# PCB-BI8-1x12SC3.net
KiCad netlist of a schematic drawn in EAGLE
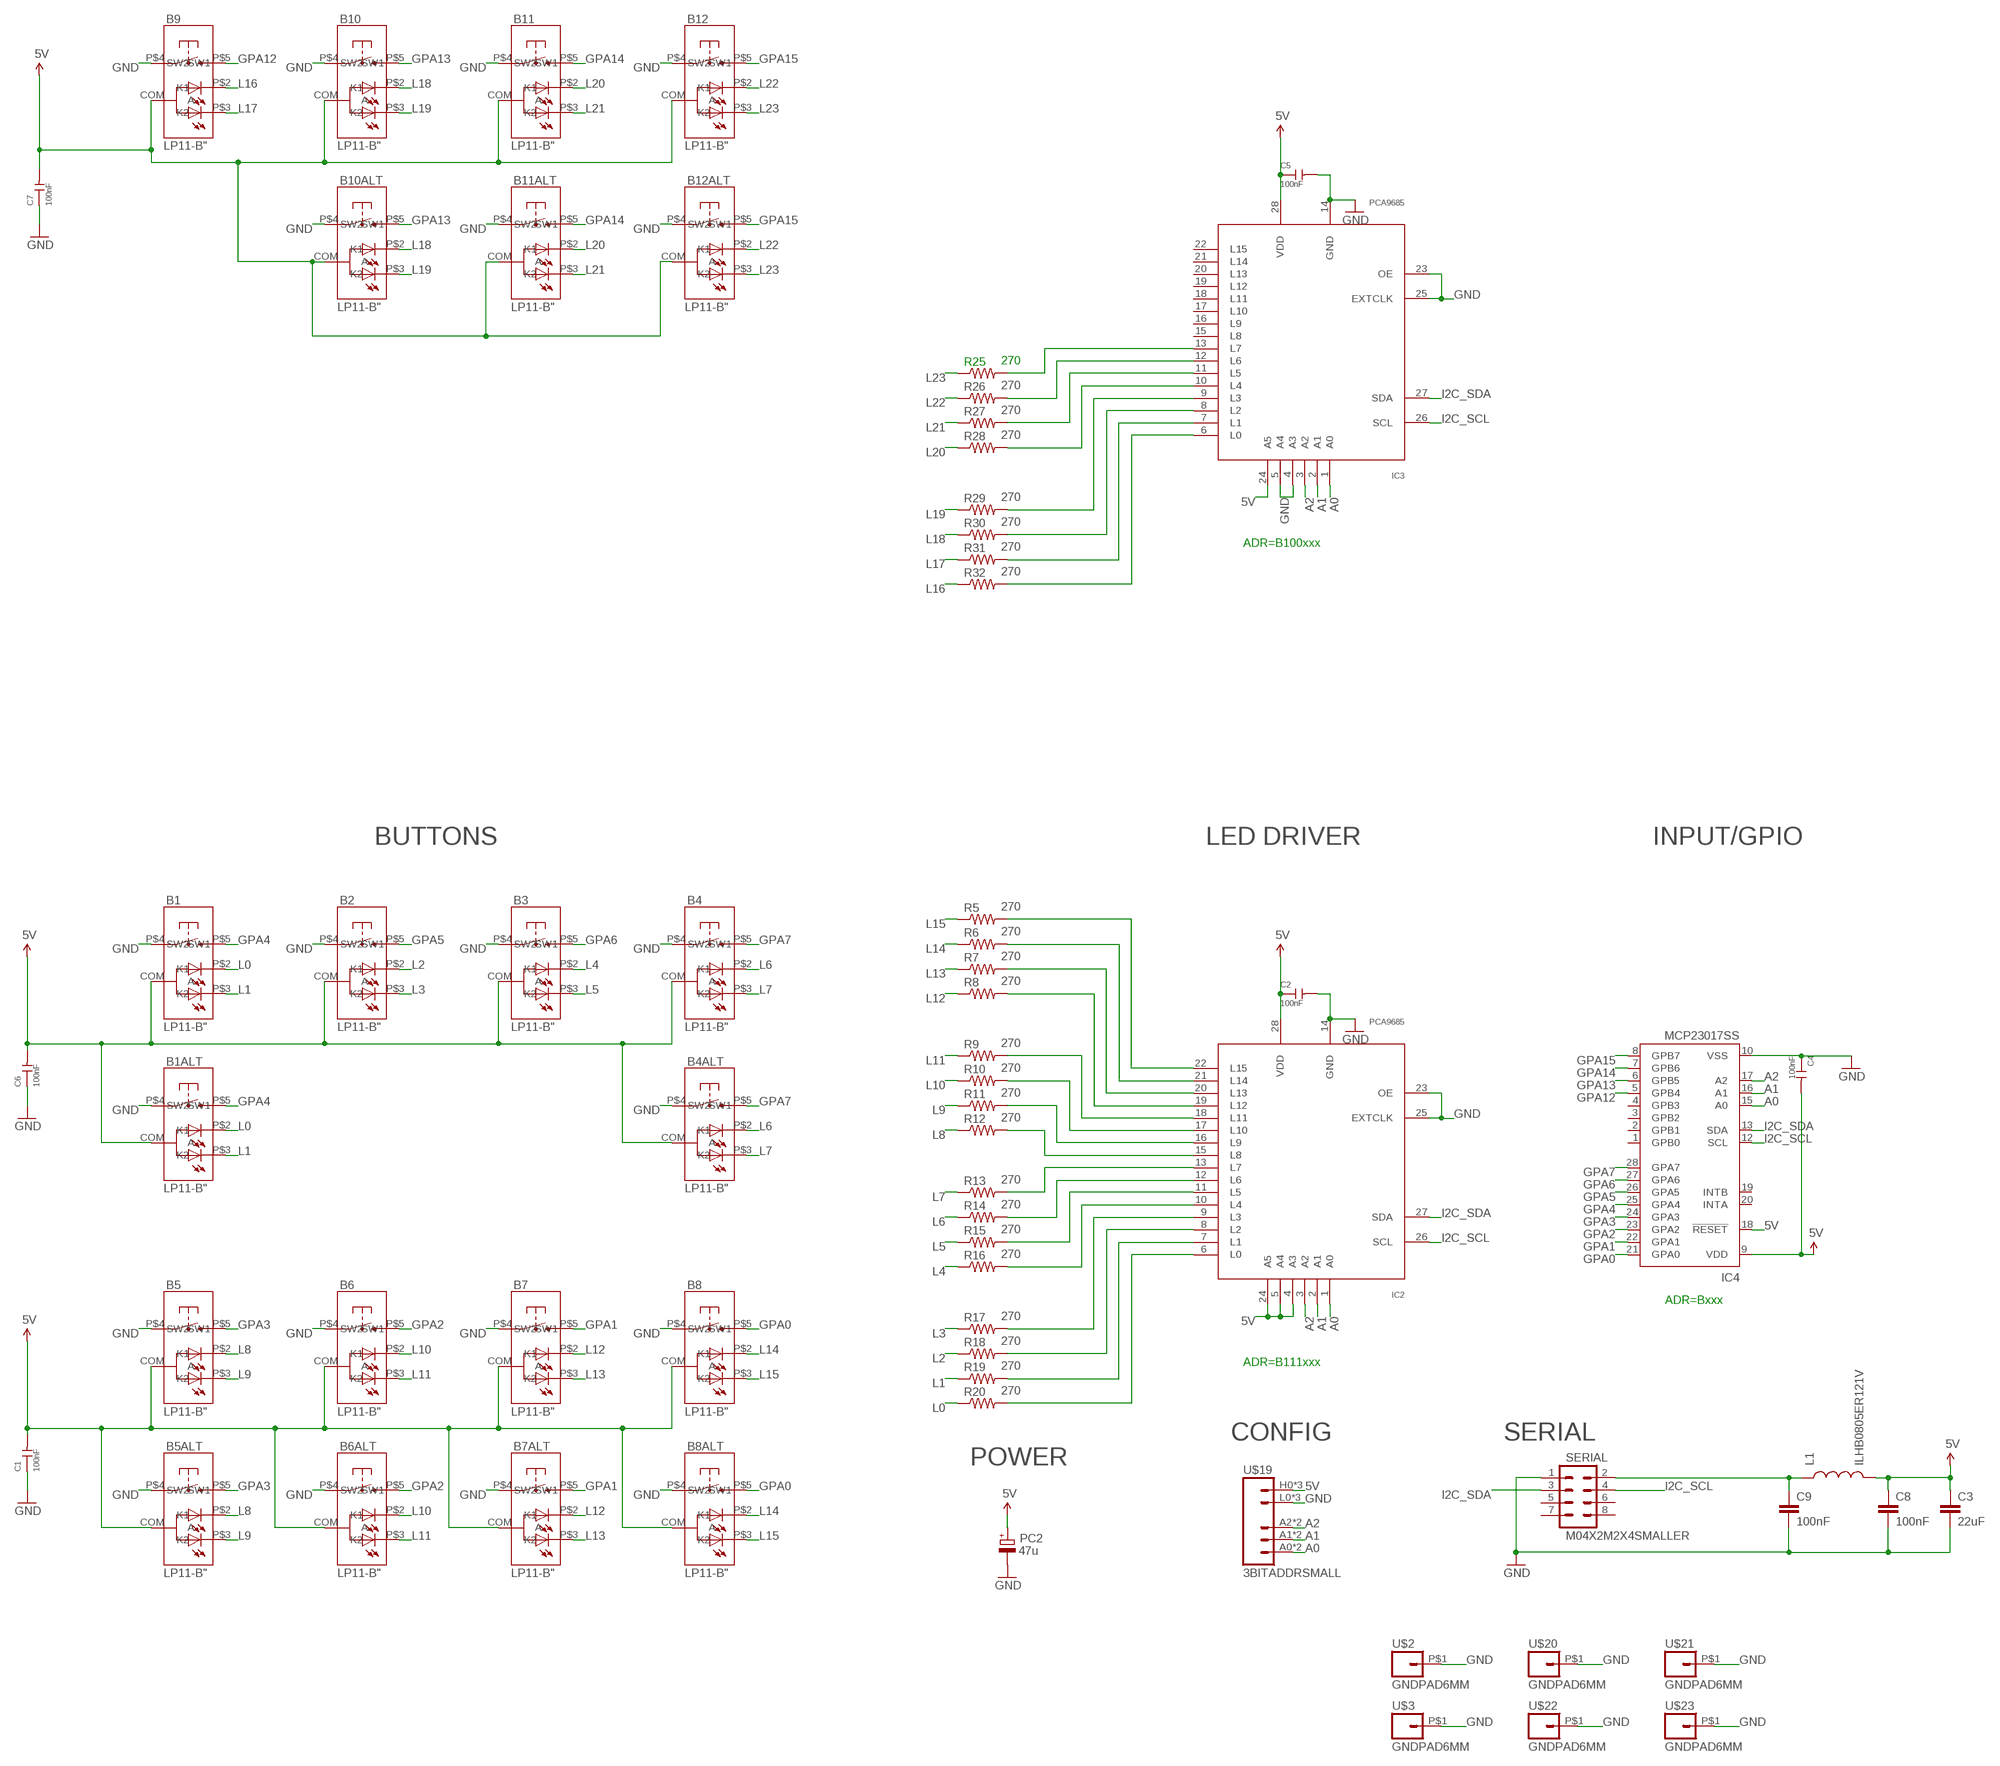
[diagram p0: schematic, sheet 1]

(export (version "E")
  (design (tool "Eeschema 10.0.6"))
  (components
    (comp (ref "B1")
      (value "LP11-B\"")
      (footprint "eagle-import:LP11")
      (libsource (lib "eagle-import") (part "LP11-B{dblquote}"))
    )
    (comp (ref "B1ALT")
      (value "LP11-B\"")
      (footprint "eagle-import:LP11")
      (libsource (lib "eagle-import") (part "LP11-B{dblquote}"))
    )
    (comp (ref "B2")
      (value "LP11-B\"")
      (footprint "eagle-import:LP11")
      (libsource (lib "eagle-import") (part "LP11-B{dblquote}"))
    )
    (comp (ref "B3")
      (value "LP11-B\"")
      (footprint "eagle-import:LP11")
      (libsource (lib "eagle-import") (part "LP11-B{dblquote}"))
    )
    (comp (ref "B4")
      (value "LP11-B\"")
      (footprint "eagle-import:LP11")
      (libsource (lib "eagle-import") (part "LP11-B{dblquote}"))
    )
    (comp (ref "B4ALT")
      (value "LP11-B\"")
      (footprint "eagle-import:LP11")
      (libsource (lib "eagle-import") (part "LP11-B{dblquote}"))
    )
    (comp (ref "B5")
      (value "LP11-B\"")
      (footprint "eagle-import:LP11")
      (libsource (lib "eagle-import") (part "LP11-B{dblquote}"))
    )
    (comp (ref "B5ALT")
      (value "LP11-B\"")
      (footprint "eagle-import:LP11")
      (libsource (lib "eagle-import") (part "LP11-B{dblquote}"))
    )
    (comp (ref "B6")
      (value "LP11-B\"")
      (footprint "eagle-import:LP11")
      (libsource (lib "eagle-import") (part "LP11-B{dblquote}"))
    )
    (comp (ref "B6ALT")
      (value "LP11-B\"")
      (footprint "eagle-import:LP11")
      (libsource (lib "eagle-import") (part "LP11-B{dblquote}"))
    )
    (comp (ref "B7")
      (value "LP11-B\"")
      (footprint "eagle-import:LP11")
      (libsource (lib "eagle-import") (part "LP11-B{dblquote}"))
    )
    (comp (ref "B7ALT")
      (value "LP11-B\"")
      (footprint "eagle-import:LP11")
      (libsource (lib "eagle-import") (part "LP11-B{dblquote}"))
    )
    (comp (ref "B8")
      (value "LP11-B\"")
      (footprint "eagle-import:LP11")
      (libsource (lib "eagle-import") (part "LP11-B{dblquote}"))
    )
    (comp (ref "B8ALT")
      (value "LP11-B\"")
      (footprint "eagle-import:LP11")
      (libsource (lib "eagle-import") (part "LP11-B{dblquote}"))
    )
    (comp (ref "B9")
      (value "LP11-B\"")
      (footprint "eagle-import:LP11")
      (libsource (lib "eagle-import") (part "LP11-B{dblquote}"))
    )
    (comp (ref "B10")
      (value "LP11-B\"")
      (footprint "eagle-import:LP11")
      (libsource (lib "eagle-import") (part "LP11-B{dblquote}"))
    )
    (comp (ref "B10ALT")
      (value "LP11-B\"")
      (footprint "eagle-import:LP11")
      (libsource (lib "eagle-import") (part "LP11-B{dblquote}"))
    )
    (comp (ref "B11")
      (value "LP11-B\"")
      (footprint "eagle-import:LP11")
      (libsource (lib "eagle-import") (part "LP11-B{dblquote}"))
    )
    (comp (ref "B11ALT")
      (value "LP11-B\"")
      (footprint "eagle-import:LP11")
      (libsource (lib "eagle-import") (part "LP11-B{dblquote}"))
    )
    (comp (ref "B12")
      (value "LP11-B\"")
      (footprint "eagle-import:LP11")
      (libsource (lib "eagle-import") (part "LP11-B{dblquote}"))
    )
    (comp (ref "B12ALT")
      (value "LP11-B\"")
      (footprint "eagle-import:LP11")
      (libsource (lib "eagle-import") (part "LP11-B{dblquote}"))
    )
    (comp (ref "C1")
      (value "100nF")
      (footprint "eagle-import:C0603")
      (libsource (lib "eagle-import") (part "CAP-0603"))
    )
    (comp (ref "C2")
      (value "100nF")
      (footprint "eagle-import:C0603")
      (libsource (lib "eagle-import") (part "CAP-0603"))
    )
    (comp (ref "C3")
      (value "22uF")
      (footprint "eagle-import:0805")
      (libsource (lib "eagle-import") (part "CAP0805"))
    )
    (comp (ref "C4")
      (value "100nF")
      (footprint "eagle-import:C0603")
      (libsource (lib "eagle-import") (part "CAP-0603"))
    )
    (comp (ref "C5")
      (value "100nF")
      (footprint "eagle-import:C0603")
      (libsource (lib "eagle-import") (part "CAP-0603"))
    )
    (comp (ref "C6")
      (value "100nF")
      (footprint "eagle-import:C0603")
      (libsource (lib "eagle-import") (part "CAP-0603"))
    )
    (comp (ref "C7")
      (value "100nF")
      (footprint "eagle-import:C0603")
      (libsource (lib "eagle-import") (part "CAP-0603"))
    )
    (comp (ref "C8")
      (value "100nF")
      (footprint "eagle-import:0603-CAP")
      (libsource (lib "eagle-import") (part "CAP0603-CAP"))
    )
    (comp (ref "C9")
      (value "100nF")
      (footprint "eagle-import:0603-CAP")
      (libsource (lib "eagle-import") (part "CAP0603-CAP"))
    )
    (comp (ref "IC2")
      (value "PCA9685")
      (footprint "eagle-import:TSSOP28")
      (libsource (lib "eagle-import") (part "PCA9685"))
    )
    (comp (ref "IC3")
      (value "PCA9685")
      (footprint "eagle-import:TSSOP28")
      (libsource (lib "eagle-import") (part "PCA9685"))
    )
    (comp (ref "IC4")
      (value "MCP23017SS")
      (footprint "eagle-import:SSOP28")
      (fields
        (field (name "MF") "MICROCHIP")
        (field (name "MPN") "MCP23017-E/SS")
        (field (name "MPN_1") "MCP23017-E/SS")
        (field (name "OC_FARNELL") "1467674")
        (field (name "OC_NEWARK") "31K2960")
      )
      (libsource (lib "eagle-import") (part "MCP23017SS"))
    )
    (comp (ref "L1")
      (value "ILHB0805ER121V")
      (footprint "eagle-import:0805")
      (libsource (lib "eagle-import") (part "INDUCTOR0805"))
    )
    (comp (ref "PC2")
      (value "47u")
      (footprint "eagle-import:PANASONIC_D")
      (libsource (lib "eagle-import") (part "CPOL-EUD"))
    )
    (comp (ref "R5")
      (value "270")
      (footprint "eagle-import:0603-RES")
      (libsource (lib "eagle-import") (part "RESISTOR0603-RES"))
    )
    (comp (ref "R6")
      (value "270")
      (footprint "eagle-import:0603-RES")
      (libsource (lib "eagle-import") (part "RESISTOR0603-RES"))
    )
    (comp (ref "R7")
      (value "270")
      (footprint "eagle-import:0603-RES")
      (libsource (lib "eagle-import") (part "RESISTOR0603-RES"))
    )
    (comp (ref "R8")
      (value "270")
      (footprint "eagle-import:0603-RES")
      (libsource (lib "eagle-import") (part "RESISTOR0603-RES"))
    )
    (comp (ref "R9")
      (value "270")
      (footprint "eagle-import:0603-RES")
      (libsource (lib "eagle-import") (part "RESISTOR0603-RES"))
    )
    (comp (ref "R10")
      (value "270")
      (footprint "eagle-import:0603-RES")
      (libsource (lib "eagle-import") (part "RESISTOR0603-RES"))
    )
    (comp (ref "R11")
      (value "270")
      (footprint "eagle-import:0603-RES")
      (libsource (lib "eagle-import") (part "RESISTOR0603-RES"))
    )
    (comp (ref "R12")
      (value "270")
      (footprint "eagle-import:0603-RES")
      (libsource (lib "eagle-import") (part "RESISTOR0603-RES"))
    )
    (comp (ref "R13")
      (value "270")
      (footprint "eagle-import:0603-RES")
      (libsource (lib "eagle-import") (part "RESISTOR0603-RES"))
    )
    (comp (ref "R14")
      (value "270")
      (footprint "eagle-import:0603-RES")
      (libsource (lib "eagle-import") (part "RESISTOR0603-RES"))
    )
    (comp (ref "R15")
      (value "270")
      (footprint "eagle-import:0603-RES")
      (libsource (lib "eagle-import") (part "RESISTOR0603-RES"))
    )
    (comp (ref "R16")
      (value "270")
      (footprint "eagle-import:0603-RES")
      (libsource (lib "eagle-import") (part "RESISTOR0603-RES"))
    )
    (comp (ref "R17")
      (value "270")
      (footprint "eagle-import:0603-RES")
      (libsource (lib "eagle-import") (part "RESISTOR0603-RES"))
    )
    (comp (ref "R18")
      (value "270")
      (footprint "eagle-import:0603-RES")
      (libsource (lib "eagle-import") (part "RESISTOR0603-RES"))
    )
    (comp (ref "R19")
      (value "270")
      (footprint "eagle-import:0603-RES")
      (libsource (lib "eagle-import") (part "RESISTOR0603-RES"))
    )
    (comp (ref "R20")
      (value "270")
      (footprint "eagle-import:0603-RES")
      (libsource (lib "eagle-import") (part "RESISTOR0603-RES"))
    )
    (comp (ref "R25")
      (value "270")
      (footprint "eagle-import:0603-RES")
      (libsource (lib "eagle-import") (part "RESISTOR0603-RES"))
    )
    (comp (ref "R26")
      (value "270")
      (footprint "eagle-import:0603-RES")
      (libsource (lib "eagle-import") (part "RESISTOR0603-RES"))
    )
    (comp (ref "R27")
      (value "270")
      (footprint "eagle-import:0603-RES")
      (libsource (lib "eagle-import") (part "RESISTOR0603-RES"))
    )
    (comp (ref "R28")
      (value "270")
      (footprint "eagle-import:0603-RES")
      (libsource (lib "eagle-import") (part "RESISTOR0603-RES"))
    )
    (comp (ref "R29")
      (value "270")
      (footprint "eagle-import:0603-RES")
      (libsource (lib "eagle-import") (part "RESISTOR0603-RES"))
    )
    (comp (ref "R30")
      (value "270")
      (footprint "eagle-import:0603-RES")
      (libsource (lib "eagle-import") (part "RESISTOR0603-RES"))
    )
    (comp (ref "R31")
      (value "270")
      (footprint "eagle-import:0603-RES")
      (libsource (lib "eagle-import") (part "RESISTOR0603-RES"))
    )
    (comp (ref "R32")
      (value "270")
      (footprint "eagle-import:0603-RES")
      (libsource (lib "eagle-import") (part "RESISTOR0603-RES"))
    )
    (comp (ref "SERIAL")
      (value "M04X2M2X4SMALLER")
      (footprint "eagle-import:M2X4SMALLER")
      (libsource (lib "eagle-import") (part "M04X2M2X4SMALLER"))
    )
    (comp (ref "U$2")
      (value "GNDPAD6MM")
      (footprint "eagle-import:3.2MMPAD6MM")
      (libsource (lib "eagle-import") (part "GNDPAD6MM"))
    )
    (comp (ref "U$3")
      (value "GNDPAD6MM")
      (footprint "eagle-import:3.2MMPAD6MM")
      (libsource (lib "eagle-import") (part "GNDPAD6MM"))
    )
    (comp (ref "U$19")
      (value "3BITADDRSMALL")
      (footprint "eagle-import:3BITADDR_SMALL")
      (libsource (lib "eagle-import") (part "3BITADDRSMALL"))
    )
    (comp (ref "U$20")
      (value "GNDPAD6MM")
      (footprint "eagle-import:3.2MMPAD6MM")
      (libsource (lib "eagle-import") (part "GNDPAD6MM"))
    )
    (comp (ref "U$21")
      (value "GNDPAD6MM")
      (footprint "eagle-import:3.2MMPAD6MM")
      (libsource (lib "eagle-import") (part "GNDPAD6MM"))
    )
    (comp (ref "U$22")
      (value "GNDPAD6MM")
      (footprint "eagle-import:3.2MMPAD6MM")
      (libsource (lib "eagle-import") (part "GNDPAD6MM"))
    )
    (comp (ref "U$23")
      (value "GNDPAD6MM")
      (footprint "eagle-import:3.2MMPAD6MM")
      (libsource (lib "eagle-import") (part "GNDPAD6MM"))
    )
  )
  (nets
    (net (code "1") (name "/A0") (class "Default")
      (node (ref "IC2") (pin "1") (pinfunction "A0_1") (pintype "input"))
      (node (ref "IC3") (pin "1") (pinfunction "A0_1") (pintype "input"))
      (node (ref "IC4") (pin "15") (pinfunction "A0_15") (pintype "input"))
      (node (ref "U$19") (pin "A0") (pinfunction "A0_A0") (pintype "passive"))
      (node (ref "U$19") (pin "AS0") (pinfunction "A0_AS0") (pintype "passive"))
    )
    (net (code "2") (name "/A1") (class "Default")
      (node (ref "IC2") (pin "2") (pinfunction "A1_2") (pintype "input"))
      (node (ref "IC3") (pin "2") (pinfunction "A1_2") (pintype "input"))
      (node (ref "IC4") (pin "16") (pinfunction "A1_16") (pintype "input"))
      (node (ref "U$19") (pin "A1") (pinfunction "A1_A1") (pintype "passive"))
      (node (ref "U$19") (pin "AS1") (pinfunction "A1_AS1") (pintype "passive"))
    )
    (net (code "3") (name "/A2") (class "Default")
      (node (ref "IC2") (pin "3") (pinfunction "A2_3") (pintype "input"))
      (node (ref "IC3") (pin "3") (pinfunction "A2_3") (pintype "input"))
      (node (ref "IC4") (pin "17") (pinfunction "A2_17") (pintype "input"))
      (node (ref "U$19") (pin "A2") (pinfunction "A2_A2") (pintype "passive"))
      (node (ref "U$19") (pin "AS2") (pinfunction "A2_AS2") (pintype "passive"))
    )
    (net (code "4") (name "/GPA0") (class "Default")
      (node (ref "B8") (pin "P$5") (pinfunction "SW2_P$5") (pintype "bidirectional"))
      (node (ref "B8ALT") (pin "P$5") (pinfunction "SW2_P$5") (pintype "bidirectional"))
      (node (ref "IC4") (pin "21") (pinfunction "GPA0_21") (pintype "bidirectional"))
    )
    (net (code "5") (name "/GPA1") (class "Default")
      (node (ref "B7") (pin "P$5") (pinfunction "SW2_P$5") (pintype "bidirectional"))
      (node (ref "B7ALT") (pin "P$5") (pinfunction "SW2_P$5") (pintype "bidirectional"))
      (node (ref "IC4") (pin "22") (pinfunction "GPA1_22") (pintype "bidirectional"))
    )
    (net (code "6") (name "/GPA2") (class "Default")
      (node (ref "B6") (pin "P$5") (pinfunction "SW2_P$5") (pintype "bidirectional"))
      (node (ref "B6ALT") (pin "P$5") (pinfunction "SW2_P$5") (pintype "bidirectional"))
      (node (ref "IC4") (pin "23") (pinfunction "GPA2_23") (pintype "bidirectional"))
    )
    (net (code "7") (name "/GPA3") (class "Default")
      (node (ref "B5") (pin "P$5") (pinfunction "SW2_P$5") (pintype "bidirectional"))
      (node (ref "B5ALT") (pin "P$5") (pinfunction "SW2_P$5") (pintype "bidirectional"))
      (node (ref "IC4") (pin "24") (pinfunction "GPA3_24") (pintype "bidirectional"))
    )
    (net (code "8") (name "/GPA4") (class "Default")
      (node (ref "B1") (pin "P$5") (pinfunction "SW2_P$5") (pintype "bidirectional"))
      (node (ref "B1ALT") (pin "P$5") (pinfunction "SW2_P$5") (pintype "bidirectional"))
      (node (ref "IC4") (pin "25") (pinfunction "GPA4_25") (pintype "bidirectional"))
    )
    (net (code "9") (name "/GPA5") (class "Default")
      (node (ref "B2") (pin "P$5") (pinfunction "SW2_P$5") (pintype "bidirectional"))
      (node (ref "IC4") (pin "26") (pinfunction "GPA5_26") (pintype "bidirectional"))
    )
    (net (code "10") (name "/GPA6") (class "Default")
      (node (ref "B3") (pin "P$5") (pinfunction "SW2_P$5") (pintype "bidirectional"))
      (node (ref "IC4") (pin "27") (pinfunction "GPA6_27") (pintype "bidirectional"))
    )
    (net (code "11") (name "/GPA7") (class "Default")
      (node (ref "B4") (pin "P$5") (pinfunction "SW2_P$5") (pintype "bidirectional"))
      (node (ref "B4ALT") (pin "P$5") (pinfunction "SW2_P$5") (pintype "bidirectional"))
      (node (ref "IC4") (pin "28") (pinfunction "GPA7_28") (pintype "bidirectional"))
    )
    (net (code "12") (name "/GPA12") (class "Default")
      (node (ref "B9") (pin "P$5") (pinfunction "SW2_P$5") (pintype "bidirectional"))
      (node (ref "IC4") (pin "5") (pinfunction "GPB4_5") (pintype "bidirectional"))
    )
    (net (code "13") (name "/GPA13") (class "Default")
      (node (ref "B10") (pin "P$5") (pinfunction "SW2_P$5") (pintype "bidirectional"))
      (node (ref "B10ALT") (pin "P$5") (pinfunction "SW2_P$5") (pintype "bidirectional"))
      (node (ref "IC4") (pin "6") (pinfunction "GPB5_6") (pintype "bidirectional"))
    )
    (net (code "14") (name "/GPA14") (class "Default")
      (node (ref "B11") (pin "P$5") (pinfunction "SW2_P$5") (pintype "bidirectional"))
      (node (ref "B11ALT") (pin "P$5") (pinfunction "SW2_P$5") (pintype "bidirectional"))
      (node (ref "IC4") (pin "7") (pinfunction "GPB6_7") (pintype "bidirectional"))
    )
    (net (code "15") (name "/GPA15") (class "Default")
      (node (ref "B12") (pin "P$5") (pinfunction "SW2_P$5") (pintype "bidirectional"))
      (node (ref "B12ALT") (pin "P$5") (pinfunction "SW2_P$5") (pintype "bidirectional"))
      (node (ref "IC4") (pin "8") (pinfunction "GPB7_8") (pintype "bidirectional"))
    )
    (net (code "16") (name "/I2C_SCL") (class "Default")
      (node (ref "IC2") (pin "26") (pinfunction "SCL_26") (pintype "input"))
      (node (ref "IC3") (pin "26") (pinfunction "SCL_26") (pintype "input"))
      (node (ref "IC4") (pin "12") (pinfunction "SCL_12") (pintype "input"))
      (node (ref "SERIAL") (pin "4") (pinfunction "4_4") (pintype "passive"))
    )
    (net (code "17") (name "/I2C_SDA") (class "Default")
      (node (ref "IC2") (pin "27") (pinfunction "SDA_27") (pintype "input"))
      (node (ref "IC3") (pin "27") (pinfunction "SDA_27") (pintype "input"))
      (node (ref "IC4") (pin "13") (pinfunction "SDA_13") (pintype "bidirectional"))
      (node (ref "SERIAL") (pin "3") (pinfunction "3_3") (pintype "passive"))
    )
    (net (code "18") (name "/L0") (class "Default")
      (node (ref "B1") (pin "P$2") (pinfunction "K1_P$2") (pintype "bidirectional"))
      (node (ref "B1ALT") (pin "P$2") (pinfunction "K1_P$2") (pintype "bidirectional"))
      (node (ref "R20") (pin "1") (pinfunction "1_1") (pintype "passive"))
    )
    (net (code "19") (name "/L1") (class "Default")
      (node (ref "B1") (pin "P$3") (pinfunction "K2_P$3") (pintype "bidirectional"))
      (node (ref "B1ALT") (pin "P$3") (pinfunction "K2_P$3") (pintype "bidirectional"))
      (node (ref "R19") (pin "1") (pinfunction "1_1") (pintype "passive"))
    )
    (net (code "20") (name "/L2") (class "Default")
      (node (ref "B2") (pin "P$2") (pinfunction "K1_P$2") (pintype "bidirectional"))
      (node (ref "R18") (pin "1") (pinfunction "1_1") (pintype "passive"))
    )
    (net (code "21") (name "/L3") (class "Default")
      (node (ref "B2") (pin "P$3") (pinfunction "K2_P$3") (pintype "bidirectional"))
      (node (ref "R17") (pin "1") (pinfunction "1_1") (pintype "passive"))
    )
    (net (code "22") (name "/L4") (class "Default")
      (node (ref "B3") (pin "P$2") (pinfunction "K1_P$2") (pintype "bidirectional"))
      (node (ref "R16") (pin "1") (pinfunction "1_1") (pintype "passive"))
    )
    (net (code "23") (name "/L5") (class "Default")
      (node (ref "B3") (pin "P$3") (pinfunction "K2_P$3") (pintype "bidirectional"))
      (node (ref "R15") (pin "1") (pinfunction "1_1") (pintype "passive"))
    )
    (net (code "24") (name "/L6") (class "Default")
      (node (ref "B4") (pin "P$2") (pinfunction "K1_P$2") (pintype "bidirectional"))
      (node (ref "B4ALT") (pin "P$2") (pinfunction "K1_P$2") (pintype "bidirectional"))
      (node (ref "R14") (pin "1") (pinfunction "1_1") (pintype "passive"))
    )
    (net (code "25") (name "/L7") (class "Default")
      (node (ref "B4") (pin "P$3") (pinfunction "K2_P$3") (pintype "bidirectional"))
      (node (ref "B4ALT") (pin "P$3") (pinfunction "K2_P$3") (pintype "bidirectional"))
      (node (ref "R13") (pin "1") (pinfunction "1_1") (pintype "passive"))
    )
    (net (code "26") (name "/L8") (class "Default")
      (node (ref "B5") (pin "P$2") (pinfunction "K1_P$2") (pintype "bidirectional"))
      (node (ref "B5ALT") (pin "P$2") (pinfunction "K1_P$2") (pintype "bidirectional"))
      (node (ref "R12") (pin "1") (pinfunction "1_1") (pintype "passive"))
    )
    (net (code "27") (name "/L9") (class "Default")
      (node (ref "B5") (pin "P$3") (pinfunction "K2_P$3") (pintype "bidirectional"))
      (node (ref "B5ALT") (pin "P$3") (pinfunction "K2_P$3") (pintype "bidirectional"))
      (node (ref "R11") (pin "1") (pinfunction "1_1") (pintype "passive"))
    )
    (net (code "28") (name "/L10") (class "Default")
      (node (ref "B6") (pin "P$2") (pinfunction "K1_P$2") (pintype "bidirectional"))
      (node (ref "B6ALT") (pin "P$2") (pinfunction "K1_P$2") (pintype "bidirectional"))
      (node (ref "R10") (pin "1") (pinfunction "1_1") (pintype "passive"))
    )
    (net (code "29") (name "/L11") (class "Default")
      (node (ref "B6") (pin "P$3") (pinfunction "K2_P$3") (pintype "bidirectional"))
      (node (ref "B6ALT") (pin "P$3") (pinfunction "K2_P$3") (pintype "bidirectional"))
      (node (ref "R9") (pin "1") (pinfunction "1_1") (pintype "passive"))
    )
    (net (code "30") (name "/L12") (class "Default")
      (node (ref "B7") (pin "P$2") (pinfunction "K1_P$2") (pintype "bidirectional"))
      (node (ref "B7ALT") (pin "P$2") (pinfunction "K1_P$2") (pintype "bidirectional"))
      (node (ref "R8") (pin "1") (pinfunction "1_1") (pintype "passive"))
    )
    (net (code "31") (name "/L13") (class "Default")
      (node (ref "B7") (pin "P$3") (pinfunction "K2_P$3") (pintype "bidirectional"))
      (node (ref "B7ALT") (pin "P$3") (pinfunction "K2_P$3") (pintype "bidirectional"))
      (node (ref "R7") (pin "1") (pinfunction "1_1") (pintype "passive"))
    )
    (net (code "32") (name "/L14") (class "Default")
      (node (ref "B8") (pin "P$2") (pinfunction "K1_P$2") (pintype "bidirectional"))
      (node (ref "B8ALT") (pin "P$2") (pinfunction "K1_P$2") (pintype "bidirectional"))
      (node (ref "R6") (pin "1") (pinfunction "1_1") (pintype "passive"))
    )
    (net (code "33") (name "/L15") (class "Default")
      (node (ref "B8") (pin "P$3") (pinfunction "K2_P$3") (pintype "bidirectional"))
      (node (ref "B8ALT") (pin "P$3") (pinfunction "K2_P$3") (pintype "bidirectional"))
      (node (ref "R5") (pin "1") (pinfunction "1_1") (pintype "passive"))
    )
    (net (code "34") (name "/L16") (class "Default")
      (node (ref "B9") (pin "P$2") (pinfunction "K1_P$2") (pintype "bidirectional"))
      (node (ref "R32") (pin "1") (pinfunction "1_1") (pintype "passive"))
    )
    (net (code "35") (name "/L17") (class "Default")
      (node (ref "B9") (pin "P$3") (pinfunction "K2_P$3") (pintype "bidirectional"))
      (node (ref "R31") (pin "1") (pinfunction "1_1") (pintype "passive"))
    )
    (net (code "36") (name "/L18") (class "Default")
      (node (ref "B10") (pin "P$2") (pinfunction "K1_P$2") (pintype "bidirectional"))
      (node (ref "B10ALT") (pin "P$2") (pinfunction "K1_P$2") (pintype "bidirectional"))
      (node (ref "R30") (pin "1") (pinfunction "1_1") (pintype "passive"))
    )
    (net (code "37") (name "/L19") (class "Default")
      (node (ref "B10") (pin "P$3") (pinfunction "K2_P$3") (pintype "bidirectional"))
      (node (ref "B10ALT") (pin "P$3") (pinfunction "K2_P$3") (pintype "bidirectional"))
      (node (ref "R29") (pin "1") (pinfunction "1_1") (pintype "passive"))
    )
    (net (code "38") (name "/L20") (class "Default")
      (node (ref "B11") (pin "P$2") (pinfunction "K1_P$2") (pintype "bidirectional"))
      (node (ref "B11ALT") (pin "P$2") (pinfunction "K1_P$2") (pintype "bidirectional"))
      (node (ref "R28") (pin "1") (pinfunction "1_1") (pintype "passive"))
    )
    (net (code "39") (name "/L21") (class "Default")
      (node (ref "B11") (pin "P$3") (pinfunction "K2_P$3") (pintype "bidirectional"))
      (node (ref "B11ALT") (pin "P$3") (pinfunction "K2_P$3") (pintype "bidirectional"))
      (node (ref "R27") (pin "1") (pinfunction "1_1") (pintype "passive"))
    )
    (net (code "40") (name "/L22") (class "Default")
      (node (ref "B12") (pin "P$2") (pinfunction "K1_P$2") (pintype "bidirectional"))
      (node (ref "B12ALT") (pin "P$2") (pinfunction "K1_P$2") (pintype "bidirectional"))
      (node (ref "R26") (pin "1") (pinfunction "1_1") (pintype "passive"))
    )
    (net (code "41") (name "/L23") (class "Default")
      (node (ref "B12") (pin "P$3") (pinfunction "K2_P$3") (pintype "bidirectional"))
      (node (ref "B12ALT") (pin "P$3") (pinfunction "K2_P$3") (pintype "bidirectional"))
      (node (ref "R25") (pin "1") (pinfunction "1_1") (pintype "passive"))
    )
    (net (code "42") (name "5V") (class "Default")
      (node (ref "B1") (pin "COM") (pinfunction "A_COM") (pintype "bidirectional"))
      (node (ref "B10") (pin "COM") (pinfunction "A_COM") (pintype "bidirectional"))
      (node (ref "B10ALT") (pin "COM") (pinfunction "A_COM") (pintype "bidirectional"))
      (node (ref "B11") (pin "COM") (pinfunction "A_COM") (pintype "bidirectional"))
      (node (ref "B11ALT") (pin "COM") (pinfunction "A_COM") (pintype "bidirectional"))
      (node (ref "B12") (pin "COM") (pinfunction "A_COM") (pintype "bidirectional"))
      (node (ref "B12ALT") (pin "COM") (pinfunction "A_COM") (pintype "bidirectional"))
      (node (ref "B1ALT") (pin "COM") (pinfunction "A_COM") (pintype "bidirectional"))
      (node (ref "B2") (pin "COM") (pinfunction "A_COM") (pintype "bidirectional"))
      (node (ref "B3") (pin "COM") (pinfunction "A_COM") (pintype "bidirectional"))
      (node (ref "B4") (pin "COM") (pinfunction "A_COM") (pintype "bidirectional"))
      (node (ref "B4ALT") (pin "COM") (pinfunction "A_COM") (pintype "bidirectional"))
      (node (ref "B5") (pin "COM") (pinfunction "A_COM") (pintype "bidirectional"))
      (node (ref "B5ALT") (pin "COM") (pinfunction "A_COM") (pintype "bidirectional"))
      (node (ref "B6") (pin "COM") (pinfunction "A_COM") (pintype "bidirectional"))
      (node (ref "B6ALT") (pin "COM") (pinfunction "A_COM") (pintype "bidirectional"))
      (node (ref "B7") (pin "COM") (pinfunction "A_COM") (pintype "bidirectional"))
      (node (ref "B7ALT") (pin "COM") (pinfunction "A_COM") (pintype "bidirectional"))
      (node (ref "B8") (pin "COM") (pinfunction "A_COM") (pintype "bidirectional"))
      (node (ref "B8ALT") (pin "COM") (pinfunction "A_COM") (pintype "bidirectional"))
      (node (ref "B9") (pin "COM") (pinfunction "A_COM") (pintype "bidirectional"))
      (node (ref "C1") (pin "2") (pinfunction "2_2") (pintype "passive"))
      (node (ref "C2") (pin "1") (pinfunction "1_1") (pintype "passive"))
      (node (ref "C3") (pin "1") (pinfunction "1_1") (pintype "passive"))
      (node (ref "C4") (pin "2") (pinfunction "2_2") (pintype "passive"))
      (node (ref "C5") (pin "1") (pinfunction "1_1") (pintype "passive"))
      (node (ref "C6") (pin "2") (pinfunction "2_2") (pintype "passive"))
      (node (ref "C7") (pin "2") (pinfunction "2_2") (pintype "passive"))
      (node (ref "C8") (pin "1") (pinfunction "1_1") (pintype "passive"))
      (node (ref "IC2") (pin "24") (pinfunction "A5_24") (pintype "input"))
      (node (ref "IC2") (pin "28") (pinfunction "VDD_28") (pintype "power_in"))
      (node (ref "IC2") (pin "4") (pinfunction "A3_4") (pintype "input"))
      (node (ref "IC2") (pin "5") (pinfunction "A4_5") (pintype "input"))
      (node (ref "IC3") (pin "24") (pinfunction "A5_24") (pintype "input"))
      (node (ref "IC3") (pin "28") (pinfunction "VDD_28") (pintype "power_in"))
      (node (ref "IC4") (pin "18") (pinfunction "~{RESET}_18") (pintype "input"))
      (node (ref "IC4") (pin "9") (pinfunction "VDD_9") (pintype "power_in"))
      (node (ref "L1") (pin "2") (pinfunction "2_2") (pintype "passive"))
      (node (ref "PC2") (pin "+") (pinfunction "+_+") (pintype "passive"))
      (node (ref "U$19") (pin "H0") (pinfunction "VCC_H0") (pintype "passive"))
      (node (ref "U$19") (pin "H1") (pinfunction "VCC_H1") (pintype "passive"))
      (node (ref "U$19") (pin "H2") (pinfunction "VCC_H2") (pintype "passive"))
    )
    (net (code "43") (name "GND") (class "Default")
      (node (ref "B1") (pin "P$4") (pinfunction "SW1_P$4") (pintype "bidirectional"))
      (node (ref "B10") (pin "P$4") (pinfunction "SW1_P$4") (pintype "bidirectional"))
      (node (ref "B10ALT") (pin "P$4") (pinfunction "SW1_P$4") (pintype "bidirectional"))
      (node (ref "B11") (pin "P$4") (pinfunction "SW1_P$4") (pintype "bidirectional"))
      (node (ref "B11ALT") (pin "P$4") (pinfunction "SW1_P$4") (pintype "bidirectional"))
      (node (ref "B12") (pin "P$4") (pinfunction "SW1_P$4") (pintype "bidirectional"))
      (node (ref "B12ALT") (pin "P$4") (pinfunction "SW1_P$4") (pintype "bidirectional"))
      (node (ref "B1ALT") (pin "P$4") (pinfunction "SW1_P$4") (pintype "bidirectional"))
      (node (ref "B2") (pin "P$4") (pinfunction "SW1_P$4") (pintype "bidirectional"))
      (node (ref "B3") (pin "P$4") (pinfunction "SW1_P$4") (pintype "bidirectional"))
      (node (ref "B4") (pin "P$4") (pinfunction "SW1_P$4") (pintype "bidirectional"))
      (node (ref "B4ALT") (pin "P$4") (pinfunction "SW1_P$4") (pintype "bidirectional"))
      (node (ref "B5") (pin "P$4") (pinfunction "SW1_P$4") (pintype "bidirectional"))
      (node (ref "B5ALT") (pin "P$4") (pinfunction "SW1_P$4") (pintype "bidirectional"))
      (node (ref "B6") (pin "P$4") (pinfunction "SW1_P$4") (pintype "bidirectional"))
      (node (ref "B6ALT") (pin "P$4") (pinfunction "SW1_P$4") (pintype "bidirectional"))
      (node (ref "B7") (pin "P$4") (pinfunction "SW1_P$4") (pintype "bidirectional"))
      (node (ref "B7ALT") (pin "P$4") (pinfunction "SW1_P$4") (pintype "bidirectional"))
      (node (ref "B8") (pin "P$4") (pinfunction "SW1_P$4") (pintype "bidirectional"))
      (node (ref "B8ALT") (pin "P$4") (pinfunction "SW1_P$4") (pintype "bidirectional"))
      (node (ref "B9") (pin "P$4") (pinfunction "SW1_P$4") (pintype "bidirectional"))
      (node (ref "C1") (pin "1") (pinfunction "1_1") (pintype "passive"))
      (node (ref "C2") (pin "2") (pinfunction "2_2") (pintype "passive"))
      (node (ref "C3") (pin "2") (pinfunction "2_2") (pintype "passive"))
      (node (ref "C4") (pin "1") (pinfunction "1_1") (pintype "passive"))
      (node (ref "C5") (pin "2") (pinfunction "2_2") (pintype "passive"))
      (node (ref "C6") (pin "1") (pinfunction "1_1") (pintype "passive"))
      (node (ref "C7") (pin "1") (pinfunction "1_1") (pintype "passive"))
      (node (ref "C8") (pin "2") (pinfunction "2_2") (pintype "passive"))
      (node (ref "C9") (pin "2") (pinfunction "2_2") (pintype "passive"))
      (node (ref "IC2") (pin "14") (pinfunction "GND_14") (pintype "power_in"))
      (node (ref "IC2") (pin "23") (pinfunction "OE_23") (pintype "input"))
      (node (ref "IC2") (pin "25") (pinfunction "EXTCLK_25") (pintype "input"))
      (node (ref "IC3") (pin "14") (pinfunction "GND_14") (pintype "power_in"))
      (node (ref "IC3") (pin "23") (pinfunction "OE_23") (pintype "input"))
      (node (ref "IC3") (pin "25") (pinfunction "EXTCLK_25") (pintype "input"))
      (node (ref "IC3") (pin "4") (pinfunction "A3_4") (pintype "input"))
      (node (ref "IC3") (pin "5") (pinfunction "A4_5") (pintype "input"))
      (node (ref "IC4") (pin "10") (pinfunction "VSS_10") (pintype "power_in"))
      (node (ref "PC2") (pin "-") (pinfunction "-_-") (pintype "passive"))
      (node (ref "SERIAL") (pin "1") (pinfunction "1_1") (pintype "passive"))
      (node (ref "U$19") (pin "L0") (pinfunction "GND_L0") (pintype "passive"))
      (node (ref "U$19") (pin "L1") (pinfunction "GND_L1") (pintype "passive"))
      (node (ref "U$19") (pin "L2") (pinfunction "GND_L2") (pintype "passive"))
      (node (ref "U$2") (pin "P$1") (pinfunction "1_P$1") (pintype "passive"))
      (node (ref "U$20") (pin "P$1") (pinfunction "1_P$1") (pintype "passive"))
      (node (ref "U$21") (pin "P$1") (pinfunction "1_P$1") (pintype "passive"))
      (node (ref "U$22") (pin "P$1") (pinfunction "1_P$1") (pintype "passive"))
      (node (ref "U$23") (pin "P$1") (pinfunction "1_P$1") (pintype "passive"))
      (node (ref "U$3") (pin "P$1") (pinfunction "1_P$1") (pintype "passive"))
    )
    (net (code "44") (name "Net-(C9-Pad1)") (class "Default")
      (node (ref "C9") (pin "1") (pinfunction "1_1") (pintype "passive"))
      (node (ref "L1") (pin "1") (pinfunction "1_1") (pintype "passive"))
      (node (ref "SERIAL") (pin "2") (pinfunction "2_2") (pintype "passive"))
    )
    (net (code "45") (name "Net-(IC2-L0)") (class "Default")
      (node (ref "IC2") (pin "6") (pinfunction "L0_6") (pintype "output"))
      (node (ref "R20") (pin "2") (pinfunction "2_2") (pintype "passive"))
    )
    (net (code "46") (name "Net-(IC2-L1)") (class "Default")
      (node (ref "IC2") (pin "7") (pinfunction "L1_7") (pintype "output"))
      (node (ref "R19") (pin "2") (pinfunction "2_2") (pintype "passive"))
    )
    (net (code "47") (name "Net-(IC2-L2)") (class "Default")
      (node (ref "IC2") (pin "8") (pinfunction "L2_8") (pintype "output"))
      (node (ref "R18") (pin "2") (pinfunction "2_2") (pintype "passive"))
    )
    (net (code "48") (name "Net-(IC2-L3)") (class "Default")
      (node (ref "IC2") (pin "9") (pinfunction "L3_9") (pintype "output"))
      (node (ref "R17") (pin "2") (pinfunction "2_2") (pintype "passive"))
    )
    (net (code "49") (name "Net-(IC2-L4)") (class "Default")
      (node (ref "IC2") (pin "10") (pinfunction "L4_10") (pintype "output"))
      (node (ref "R16") (pin "2") (pinfunction "2_2") (pintype "passive"))
    )
    (net (code "50") (name "Net-(IC2-L5)") (class "Default")
      (node (ref "IC2") (pin "11") (pinfunction "L5_11") (pintype "output"))
      (node (ref "R15") (pin "2") (pinfunction "2_2") (pintype "passive"))
    )
    (net (code "51") (name "Net-(IC2-L6)") (class "Default")
      (node (ref "IC2") (pin "12") (pinfunction "L6_12") (pintype "output"))
      (node (ref "R14") (pin "2") (pinfunction "2_2") (pintype "passive"))
    )
    (net (code "52") (name "Net-(IC2-L7)") (class "Default")
      (node (ref "IC2") (pin "13") (pinfunction "L7_13") (pintype "output"))
      (node (ref "R13") (pin "2") (pinfunction "2_2") (pintype "passive"))
    )
    (net (code "53") (name "Net-(IC2-L8)") (class "Default")
      (node (ref "IC2") (pin "15") (pinfunction "L8_15") (pintype "output"))
      (node (ref "R12") (pin "2") (pinfunction "2_2") (pintype "passive"))
    )
    (net (code "54") (name "Net-(IC2-L9)") (class "Default")
      (node (ref "IC2") (pin "16") (pinfunction "L9_16") (pintype "output"))
      (node (ref "R11") (pin "2") (pinfunction "2_2") (pintype "passive"))
    )
    (net (code "55") (name "Net-(IC2-L10)") (class "Default")
      (node (ref "IC2") (pin "17") (pinfunction "L10_17") (pintype "output"))
      (node (ref "R10") (pin "2") (pinfunction "2_2") (pintype "passive"))
    )
    (net (code "56") (name "Net-(IC2-L11)") (class "Default")
      (node (ref "IC2") (pin "18") (pinfunction "L11_18") (pintype "output"))
      (node (ref "R9") (pin "2") (pinfunction "2_2") (pintype "passive"))
    )
    (net (code "57") (name "Net-(IC2-L12)") (class "Default")
      (node (ref "IC2") (pin "19") (pinfunction "L12_19") (pintype "output"))
      (node (ref "R8") (pin "2") (pinfunction "2_2") (pintype "passive"))
    )
    (net (code "58") (name "Net-(IC2-L13)") (class "Default")
      (node (ref "IC2") (pin "20") (pinfunction "L13_20") (pintype "output"))
      (node (ref "R7") (pin "2") (pinfunction "2_2") (pintype "passive"))
    )
    (net (code "59") (name "Net-(IC2-L14)") (class "Default")
      (node (ref "IC2") (pin "21") (pinfunction "L14_21") (pintype "output"))
      (node (ref "R6") (pin "2") (pinfunction "2_2") (pintype "passive"))
    )
    (net (code "60") (name "Net-(IC2-L15)") (class "Default")
      (node (ref "IC2") (pin "22") (pinfunction "L15_22") (pintype "output"))
      (node (ref "R5") (pin "2") (pinfunction "2_2") (pintype "passive"))
    )
    (net (code "61") (name "Net-(IC3-L0)") (class "Default")
      (node (ref "IC3") (pin "6") (pinfunction "L0_6") (pintype "output"))
      (node (ref "R32") (pin "2") (pinfunction "2_2") (pintype "passive"))
    )
    (net (code "62") (name "Net-(IC3-L1)") (class "Default")
      (node (ref "IC3") (pin "7") (pinfunction "L1_7") (pintype "output"))
      (node (ref "R31") (pin "2") (pinfunction "2_2") (pintype "passive"))
    )
    (net (code "63") (name "Net-(IC3-L2)") (class "Default")
      (node (ref "IC3") (pin "8") (pinfunction "L2_8") (pintype "output"))
      (node (ref "R30") (pin "2") (pinfunction "2_2") (pintype "passive"))
    )
    (net (code "64") (name "Net-(IC3-L3)") (class "Default")
      (node (ref "IC3") (pin "9") (pinfunction "L3_9") (pintype "output"))
      (node (ref "R29") (pin "2") (pinfunction "2_2") (pintype "passive"))
    )
    (net (code "65") (name "Net-(IC3-L4)") (class "Default")
      (node (ref "IC3") (pin "10") (pinfunction "L4_10") (pintype "output"))
      (node (ref "R28") (pin "2") (pinfunction "2_2") (pintype "passive"))
    )
    (net (code "66") (name "Net-(IC3-L5)") (class "Default")
      (node (ref "IC3") (pin "11") (pinfunction "L5_11") (pintype "output"))
      (node (ref "R27") (pin "2") (pinfunction "2_2") (pintype "passive"))
    )
    (net (code "67") (name "Net-(IC3-L6)") (class "Default")
      (node (ref "IC3") (pin "12") (pinfunction "L6_12") (pintype "output"))
      (node (ref "R26") (pin "2") (pinfunction "2_2") (pintype "passive"))
    )
    (net (code "68") (name "Net-(IC3-L7)") (class "Default")
      (node (ref "IC3") (pin "13") (pinfunction "L7_13") (pintype "output"))
      (node (ref "R25") (pin "2") (pinfunction "2_2") (pintype "passive"))
    )
    (net (code "69") (name "unconnected-(IC3-L8-Pad15)") (class "Default")
      (node (ref "IC3") (pin "15") (pinfunction "L8_15") (pintype "output"))
    )
    (net (code "70") (name "unconnected-(IC3-L9-Pad16)") (class "Default")
      (node (ref "IC3") (pin "16") (pinfunction "L9_16") (pintype "output"))
    )
    (net (code "71") (name "unconnected-(IC3-L10-Pad17)") (class "Default")
      (node (ref "IC3") (pin "17") (pinfunction "L10_17") (pintype "output"))
    )
    (net (code "72") (name "unconnected-(IC3-L11-Pad18)") (class "Default")
      (node (ref "IC3") (pin "18") (pinfunction "L11_18") (pintype "output"))
    )
    (net (code "73") (name "unconnected-(IC3-L12-Pad19)") (class "Default")
      (node (ref "IC3") (pin "19") (pinfunction "L12_19") (pintype "output"))
    )
    (net (code "74") (name "unconnected-(IC3-L13-Pad20)") (class "Default")
      (node (ref "IC3") (pin "20") (pinfunction "L13_20") (pintype "output"))
    )
    (net (code "75") (name "unconnected-(IC3-L14-Pad21)") (class "Default")
      (node (ref "IC3") (pin "21") (pinfunction "L14_21") (pintype "output"))
    )
    (net (code "76") (name "unconnected-(IC3-L15-Pad22)") (class "Default")
      (node (ref "IC3") (pin "22") (pinfunction "L15_22") (pintype "output"))
    )
    (net (code "77") (name "unconnected-(IC4-GPB0-Pad1)") (class "Default")
      (node (ref "IC4") (pin "1") (pinfunction "GPB0_1") (pintype "bidirectional"))
    )
    (net (code "78") (name "unconnected-(IC4-GPB1-Pad2)") (class "Default")
      (node (ref "IC4") (pin "2") (pinfunction "GPB1_2") (pintype "bidirectional"))
    )
    (net (code "79") (name "unconnected-(IC4-GPB2-Pad3)") (class "Default")
      (node (ref "IC4") (pin "3") (pinfunction "GPB2_3") (pintype "bidirectional"))
    )
    (net (code "80") (name "unconnected-(IC4-GPB3-Pad4)") (class "Default")
      (node (ref "IC4") (pin "4") (pinfunction "GPB3_4") (pintype "bidirectional"))
    )
    (net (code "81") (name "unconnected-(IC4-INTA-Pad20)") (class "Default")
      (node (ref "IC4") (pin "20") (pinfunction "INTA_20") (pintype "output"))
    )
    (net (code "82") (name "unconnected-(IC4-INTB-Pad19)") (class "Default")
      (node (ref "IC4") (pin "19") (pinfunction "INTB_19") (pintype "output"))
    )
    (net (code "83") (name "unconnected-(SERIAL-Pad5)") (class "Default")
      (node (ref "SERIAL") (pin "5") (pinfunction "5_5") (pintype "passive"))
    )
    (net (code "84") (name "unconnected-(SERIAL-Pad6)") (class "Default")
      (node (ref "SERIAL") (pin "6") (pinfunction "6_6") (pintype "passive"))
    )
    (net (code "85") (name "unconnected-(SERIAL-Pad7)") (class "Default")
      (node (ref "SERIAL") (pin "7") (pinfunction "7_7") (pintype "passive"))
    )
    (net (code "86") (name "unconnected-(SERIAL-Pad8)") (class "Default")
      (node (ref "SERIAL") (pin "8") (pinfunction "8_8") (pintype "passive"))
    )
  )
)
